# rover.net
KiCad netlist of a schematic drawn in EAGLE
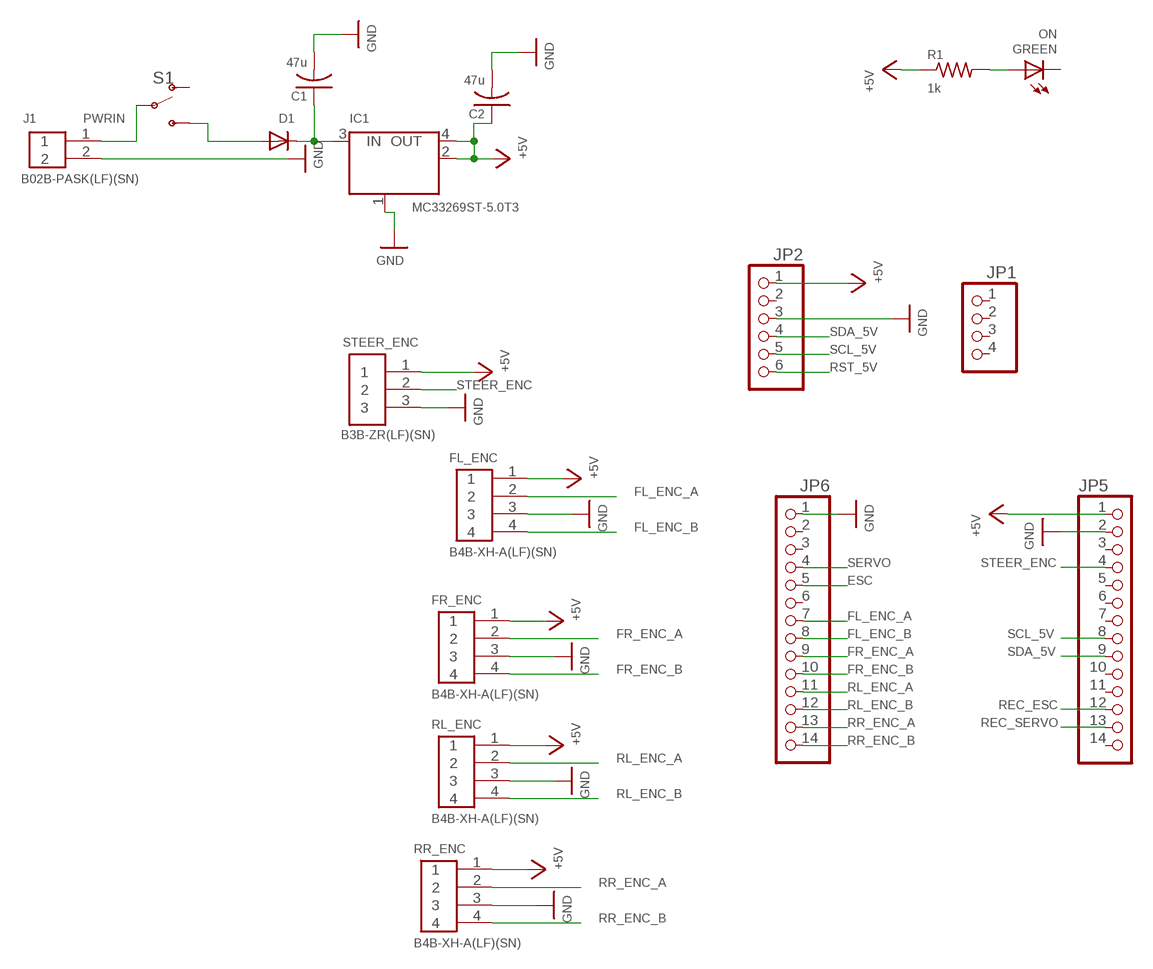
[diagram p0: schematic, sheet 1]

(export (version "E")
  (design (tool "Eeschema 10.0.6"))
  (components
    (comp (ref "C1")
      (value "47u")
      (footprint "eagle-import:C1206")
      (libsource (lib "eagle-import") (part "C-USC1206"))
    )
    (comp (ref "C2")
      (value "47u")
      (footprint "eagle-import:C1206")
      (libsource (lib "eagle-import") (part "C-USC1206"))
    )
    (comp (ref "D1")
      (value "DIODESMA")
      (footprint "eagle-import:SMADIODE")
      (libsource (lib "eagle-import") (part "DIODESMA"))
    )
    (comp (ref "FL_ENC")
      (value "B4B-XH-A(LF)(SN)")
      (footprint "eagle-import:B4B-XH-A(LF)(SN)")
      (fields
        (field (name "DIGIKEY_PARTNO") "455-2249-ND")
        (field (name "MANUFACTURER") "JST Sales America Inc.")
        (field (name "CREATED_BY") "PCBLayout.com")
      )
      (libsource (lib "eagle-import") (part "B4B-XH-A(LF)(SN)"))
    )
    (comp (ref "FR_ENC")
      (value "B4B-XH-A(LF)(SN)")
      (footprint "eagle-import:B4B-XH-A(LF)(SN)")
      (fields
        (field (name "DIGIKEY_PARTNO") "455-2249-ND")
        (field (name "MANUFACTURER") "JST Sales America Inc.")
        (field (name "CREATED_BY") "PCBLayout.com")
      )
      (libsource (lib "eagle-import") (part "B4B-XH-A(LF)(SN)"))
    )
    (comp (ref "GREEN")
      (value "ON")
      (footprint "eagle-import:CHIP-LED0805")
      (libsource (lib "eagle-import") (part "LEDCHIP-LED0805"))
    )
    (comp (ref "IC1")
      (value "MC33269ST-5.0T3")
      (footprint "eagle-import:SOT223")
      (libsource (lib "eagle-import") (part "MC33269ST-3.3T3"))
    )
    (comp (ref "J1")
      (value "B02B-PASK(LF)(SN)")
      (footprint "eagle-import:B02B-PASK(LF)(SN)")
      (fields
        (field (name "DIGIKEY_PARTNO") "455-1817-ND")
        (field (name "MANUFACTURER") "JST Sales America Inc.")
        (field (name "CREATED_BY") "PCBLayout.com")
      )
      (libsource (lib "eagle-import") (part "B02B-PASK(LF)(SN)"))
    )
    (comp (ref "JP1")
      (value "PINHD-1X4")
      (footprint "eagle-import:1X04")
      (libsource (lib "eagle-import") (part "PINHD-1X4"))
    )
    (comp (ref "JP2")
      (value "PINHD-1X6")
      (footprint "eagle-import:1X06")
      (libsource (lib "eagle-import") (part "PINHD-1X6"))
    )
    (comp (ref "JP5")
      (value "PINHD-1X14")
      (footprint "eagle-import:1X14")
      (libsource (lib "eagle-import") (part "PINHD-1X14"))
    )
    (comp (ref "JP6")
      (value "PINHD-1X14")
      (footprint "eagle-import:1X14")
      (libsource (lib "eagle-import") (part "PINHD-1X14"))
    )
    (comp (ref "R1")
      (value "1k")
      (footprint "eagle-import:R0603")
      (libsource (lib "eagle-import") (part "R-US_R0603"))
    )
    (comp (ref "RL_ENC")
      (value "B4B-XH-A(LF)(SN)")
      (footprint "eagle-import:B4B-XH-A(LF)(SN)")
      (fields
        (field (name "DIGIKEY_PARTNO") "455-2249-ND")
        (field (name "MANUFACTURER") "JST Sales America Inc.")
        (field (name "CREATED_BY") "PCBLayout.com")
      )
      (libsource (lib "eagle-import") (part "B4B-XH-A(LF)(SN)"))
    )
    (comp (ref "RR_ENC")
      (value "B4B-XH-A(LF)(SN)")
      (footprint "eagle-import:B4B-XH-A(LF)(SN)")
      (fields
        (field (name "DIGIKEY_PARTNO") "455-2249-ND")
        (field (name "MANUFACTURER") "JST Sales America Inc.")
        (field (name "CREATED_BY") "PCBLayout.com")
      )
      (libsource (lib "eagle-import") (part "B4B-XH-A(LF)(SN)"))
    )
    (comp (ref "S1")
      (value "SWITCH-SPDT-SMD-AYZ0202")
      (footprint "eagle-import:SWITCH_DPDT_SMD_AYZ0202")
      (libsource (lib "eagle-import") (part "SWITCH-SPDT-SMD-AYZ0202"))
    )
    (comp (ref "STEER_ENC")
      (value "B3B-ZR(LF)(SN)")
      (footprint "eagle-import:B3B-ZR(LF)(SN)")
      (fields
        (field (name "DIGIKEY_PARTNO") "455-1658-ND")
        (field (name "MANUFACTURER") "JST Sales America Inc.")
        (field (name "CREATED_BY") "PCBLayout.com")
      )
      (libsource (lib "eagle-import") (part "B3B-ZR(LF)(SN)"))
    )
  )
  (nets
    (net (code "1") (name "+5V") (class "Default")
      (node (ref "C2") (pin "1") (pinfunction "1_1") (pintype "passive"))
      (node (ref "FL_ENC") (pin "1") (pinfunction "1_1") (pintype "passive"))
      (node (ref "FR_ENC") (pin "1") (pinfunction "1_1") (pintype "passive"))
      (node (ref "IC1") (pin "2") (pinfunction "OUT_2") (pintype "passive"))
      (node (ref "IC1") (pin "4") (pinfunction "OUT_4") (pintype "passive"))
      (node (ref "JP2") (pin "1") (pinfunction "1_1") (pintype "passive"))
      (node (ref "JP5") (pin "1") (pinfunction "1_1") (pintype "passive"))
      (node (ref "R1") (pin "1") (pinfunction "1_1") (pintype "passive"))
      (node (ref "RL_ENC") (pin "1") (pinfunction "1_1") (pintype "passive"))
      (node (ref "RR_ENC") (pin "1") (pinfunction "1_1") (pintype "passive"))
      (node (ref "STEER_ENC") (pin "1") (pinfunction "1_1") (pintype "passive"))
    )
    (net (code "2") (name "/ESC") (class "Default")
      (node (ref "JP6") (pin "5") (pinfunction "5_5") (pintype "passive"))
    )
    (net (code "3") (name "/FL_ENC_A") (class "Default")
      (node (ref "FL_ENC") (pin "2") (pinfunction "2_2") (pintype "passive"))
      (node (ref "JP6") (pin "7") (pinfunction "7_7") (pintype "passive"))
    )
    (net (code "4") (name "/FL_ENC_B") (class "Default")
      (node (ref "FL_ENC") (pin "4") (pinfunction "4_4") (pintype "passive"))
      (node (ref "JP6") (pin "8") (pinfunction "8_8") (pintype "passive"))
    )
    (net (code "5") (name "/FR_ENC_A") (class "Default")
      (node (ref "FR_ENC") (pin "2") (pinfunction "2_2") (pintype "passive"))
      (node (ref "JP6") (pin "9") (pinfunction "9_9") (pintype "passive"))
    )
    (net (code "6") (name "/FR_ENC_B") (class "Default")
      (node (ref "FR_ENC") (pin "4") (pinfunction "4_4") (pintype "passive"))
      (node (ref "JP6") (pin "10") (pinfunction "10_10") (pintype "passive"))
    )
    (net (code "7") (name "/PWRIN") (class "Default")
      (node (ref "J1") (pin "1") (pinfunction "1_1") (pintype "passive"))
      (node (ref "S1") (pin "2") (pinfunction "P_2") (pintype "passive"))
    )
    (net (code "8") (name "/REC_ESC") (class "Default")
      (node (ref "JP5") (pin "12") (pinfunction "12_12") (pintype "passive"))
    )
    (net (code "9") (name "/REC_SERVO") (class "Default")
      (node (ref "JP5") (pin "13") (pinfunction "13_13") (pintype "passive"))
    )
    (net (code "10") (name "/RL_ENC_A") (class "Default")
      (node (ref "JP6") (pin "11") (pinfunction "11_11") (pintype "passive"))
      (node (ref "RL_ENC") (pin "2") (pinfunction "2_2") (pintype "passive"))
    )
    (net (code "11") (name "/RL_ENC_B") (class "Default")
      (node (ref "JP6") (pin "12") (pinfunction "12_12") (pintype "passive"))
      (node (ref "RL_ENC") (pin "4") (pinfunction "4_4") (pintype "passive"))
    )
    (net (code "12") (name "/RR_ENC_A") (class "Default")
      (node (ref "JP6") (pin "13") (pinfunction "13_13") (pintype "passive"))
      (node (ref "RR_ENC") (pin "2") (pinfunction "2_2") (pintype "passive"))
    )
    (net (code "13") (name "/RR_ENC_B") (class "Default")
      (node (ref "JP6") (pin "14") (pinfunction "14_14") (pintype "passive"))
      (node (ref "RR_ENC") (pin "4") (pinfunction "4_4") (pintype "passive"))
    )
    (net (code "14") (name "/RST_5V") (class "Default")
      (node (ref "JP2") (pin "6") (pinfunction "6_6") (pintype "passive"))
    )
    (net (code "15") (name "/SCL_5V") (class "Default")
      (node (ref "JP2") (pin "5") (pinfunction "5_5") (pintype "passive"))
      (node (ref "JP5") (pin "8") (pinfunction "8_8") (pintype "passive"))
    )
    (net (code "16") (name "/SDA_5V") (class "Default")
      (node (ref "JP2") (pin "4") (pinfunction "4_4") (pintype "passive"))
      (node (ref "JP5") (pin "9") (pinfunction "9_9") (pintype "passive"))
    )
    (net (code "17") (name "/SERVO") (class "Default")
      (node (ref "JP6") (pin "4") (pinfunction "4_4") (pintype "passive"))
    )
    (net (code "18") (name "/STEER_ENC") (class "Default")
      (node (ref "JP5") (pin "4") (pinfunction "4_4") (pintype "passive"))
      (node (ref "STEER_ENC") (pin "2") (pinfunction "2_2") (pintype "passive"))
    )
    (net (code "19") (name "GND") (class "Default")
      (node (ref "C1") (pin "2") (pinfunction "2_2") (pintype "passive"))
      (node (ref "C2") (pin "2") (pinfunction "2_2") (pintype "passive"))
      (node (ref "FL_ENC") (pin "3") (pinfunction "3_3") (pintype "passive"))
      (node (ref "FR_ENC") (pin "3") (pinfunction "3_3") (pintype "passive"))
      (node (ref "IC1") (pin "1") (pinfunction "GND/ADJ_1") (pintype "input"))
      (node (ref "J1") (pin "2") (pinfunction "2_2") (pintype "passive"))
      (node (ref "JP2") (pin "3") (pinfunction "3_3") (pintype "passive"))
      (node (ref "JP5") (pin "2") (pinfunction "2_2") (pintype "passive"))
      (node (ref "JP6") (pin "1") (pinfunction "1_1") (pintype "passive"))
      (node (ref "RL_ENC") (pin "3") (pinfunction "3_3") (pintype "passive"))
      (node (ref "RR_ENC") (pin "3") (pinfunction "3_3") (pintype "passive"))
      (node (ref "STEER_ENC") (pin "3") (pinfunction "3_3") (pintype "passive"))
    )
    (net (code "20") (name "Net-(GREEN-PadA)") (class "Default")
      (node (ref "GREEN") (pin "A") (pinfunction "A_A") (pintype "passive"))
      (node (ref "R1") (pin "2") (pinfunction "2_2") (pintype "passive"))
    )
    (net (code "21") (name "Net-(IC1-IN)") (class "Default")
      (node (ref "C1") (pin "1") (pinfunction "1_1") (pintype "passive"))
      (node (ref "D1") (pin "C") (pinfunction "C_C") (pintype "passive"))
      (node (ref "IC1") (pin "3") (pinfunction "IN_3") (pintype "input"))
    )
    (net (code "22") (name "Net-(S1-S)") (class "Default")
      (node (ref "D1") (pin "A") (pinfunction "A_A") (pintype "passive"))
      (node (ref "S1") (pin "3") (pinfunction "S_3") (pintype "passive"))
    )
    (net (code "23") (name "unconnected-(GREEN-PadC)") (class "Default")
      (node (ref "GREEN") (pin "C") (pinfunction "C_C") (pintype "passive"))
    )
    (net (code "24") (name "unconnected-(JP1-Pad1)") (class "Default")
      (node (ref "JP1") (pin "1") (pinfunction "1_1") (pintype "passive"))
    )
    (net (code "25") (name "unconnected-(JP1-Pad2)") (class "Default")
      (node (ref "JP1") (pin "2") (pinfunction "2_2") (pintype "passive"))
    )
    (net (code "26") (name "unconnected-(JP1-Pad3)") (class "Default")
      (node (ref "JP1") (pin "3") (pinfunction "3_3") (pintype "passive"))
    )
    (net (code "27") (name "unconnected-(JP1-Pad4)") (class "Default")
      (node (ref "JP1") (pin "4") (pinfunction "4_4") (pintype "passive"))
    )
    (net (code "28") (name "unconnected-(JP2-Pad2)") (class "Default")
      (node (ref "JP2") (pin "2") (pinfunction "2_2") (pintype "passive"))
    )
    (net (code "29") (name "unconnected-(JP5-Pad3)") (class "Default")
      (node (ref "JP5") (pin "3") (pinfunction "3_3") (pintype "passive"))
    )
    (net (code "30") (name "unconnected-(JP5-Pad5)") (class "Default")
      (node (ref "JP5") (pin "5") (pinfunction "5_5") (pintype "passive"))
    )
    (net (code "31") (name "unconnected-(JP5-Pad6)") (class "Default")
      (node (ref "JP5") (pin "6") (pinfunction "6_6") (pintype "passive"))
    )
    (net (code "32") (name "unconnected-(JP5-Pad7)") (class "Default")
      (node (ref "JP5") (pin "7") (pinfunction "7_7") (pintype "passive"))
    )
    (net (code "33") (name "unconnected-(JP5-Pad10)") (class "Default")
      (node (ref "JP5") (pin "10") (pinfunction "10_10") (pintype "passive"))
    )
    (net (code "34") (name "unconnected-(JP5-Pad11)") (class "Default")
      (node (ref "JP5") (pin "11") (pinfunction "11_11") (pintype "passive"))
    )
    (net (code "35") (name "unconnected-(JP5-Pad14)") (class "Default")
      (node (ref "JP5") (pin "14") (pinfunction "14_14") (pintype "passive"))
    )
    (net (code "36") (name "unconnected-(JP6-Pad2)") (class "Default")
      (node (ref "JP6") (pin "2") (pinfunction "2_2") (pintype "passive"))
    )
    (net (code "37") (name "unconnected-(JP6-Pad3)") (class "Default")
      (node (ref "JP6") (pin "3") (pinfunction "3_3") (pintype "passive"))
    )
    (net (code "38") (name "unconnected-(JP6-Pad6)") (class "Default")
      (node (ref "JP6") (pin "6") (pinfunction "6_6") (pintype "passive"))
    )
    (net (code "39") (name "unconnected-(S1-O-Pad1)") (class "Default")
      (node (ref "S1") (pin "1") (pinfunction "O_1") (pintype "passive"))
    )
  )
)
